# Schatten2.net
KiCad netlist of a schematic drawn in EAGLE
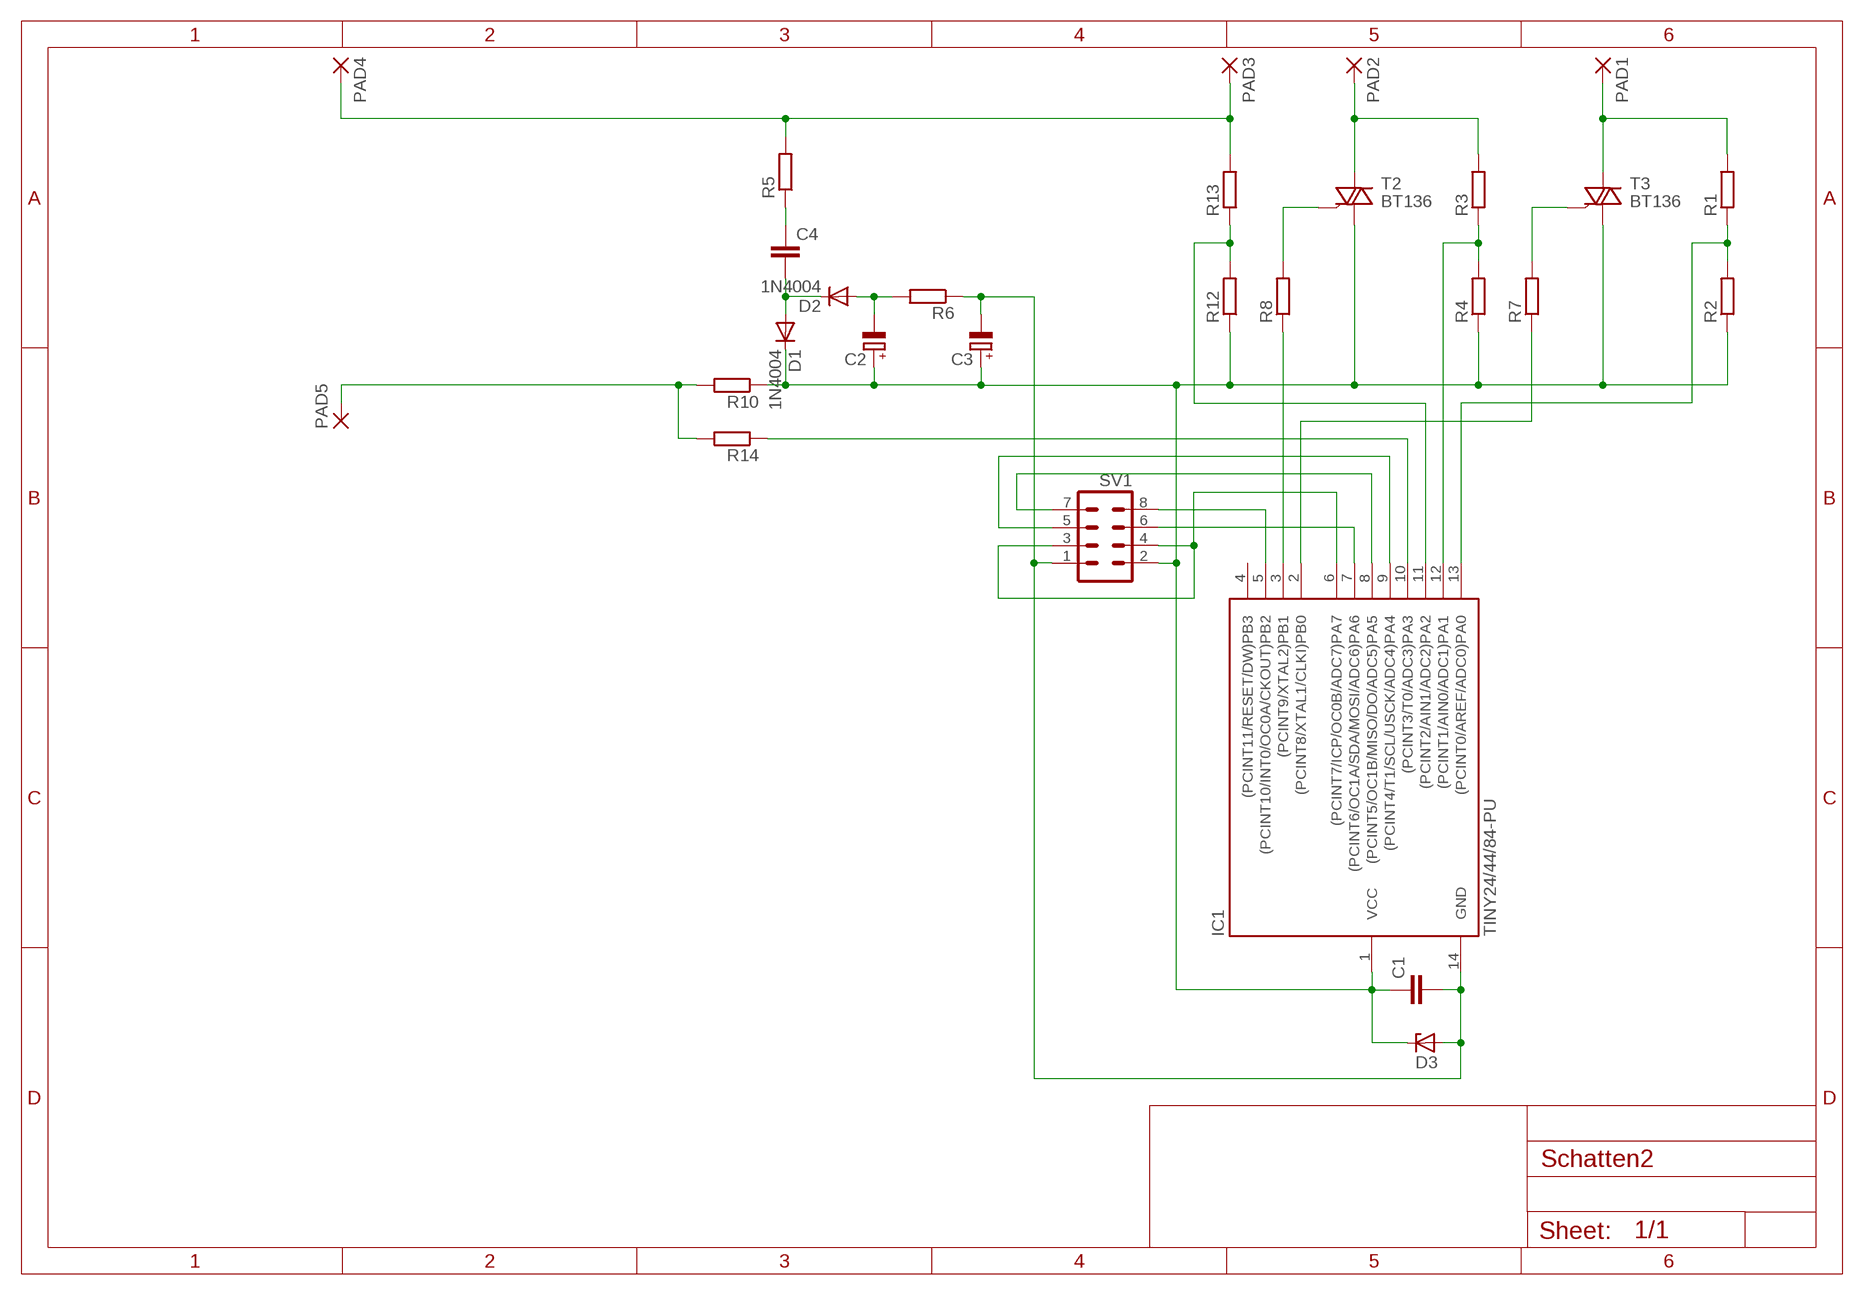
[diagram p0: schematic, sheet 1]

(export (version "E")
  (design (tool "Eeschema 10.0.6"))
  (components
    (comp (ref "C1")
      (value "C-EUC3225")
      (footprint "eagle-import:C3225")
      (libsource (lib "eagle-import") (part "C-EUC3225"))
    )
    (comp (ref "C2")
      (value "CPOL-EUE5-8.5")
      (footprint "eagle-import:E5-8,5")
      (libsource (lib "eagle-import") (part "CPOL-EUE5-8.5"))
    )
    (comp (ref "C3")
      (value "CPOL-EUE5-8.5")
      (footprint "eagle-import:E5-8,5")
      (libsource (lib "eagle-import") (part "CPOL-EUE5-8.5"))
    )
    (comp (ref "C4")
      (value "C-EU150-064X183")
      (footprint "eagle-import:C150-064X183")
      (libsource (lib "eagle-import") (part "C-EU150-064X183"))
    )
    (comp (ref "D1")
      (value "1N4004")
      (footprint "eagle-import:DO41-10")
      (libsource (lib "eagle-import") (part "1N4004"))
    )
    (comp (ref "D2")
      (value "1N4004")
      (footprint "eagle-import:DO41-10")
      (libsource (lib "eagle-import") (part "1N4004"))
    )
    (comp (ref "D3")
      (value "ZENER-DIODEZD-7.5")
      (footprint "eagle-import:ZDIO-7.5")
      (libsource (lib "eagle-import") (part "ZENER-DIODEZD-7.5"))
    )
    (comp (ref "IC1")
      (value "TINY24/44/84-PU")
      (footprint "eagle-import:DIL14")
      (libsource (lib "eagle-import") (part "TINY24/44/84-PU"))
    )
    (comp (ref "PAD1")
      (value "1,6/0,9")
      (footprint "eagle-import:1,6_0,9")
      (libsource (lib "eagle-import") (part "1,6/0,9"))
    )
    (comp (ref "PAD2")
      (value "1,6/0,9")
      (footprint "eagle-import:1,6_0,9")
      (libsource (lib "eagle-import") (part "1,6/0,9"))
    )
    (comp (ref "PAD3")
      (value "1,6/0,9")
      (footprint "eagle-import:1,6_0,9")
      (libsource (lib "eagle-import") (part "1,6/0,9"))
    )
    (comp (ref "PAD4")
      (value "1,6/0,9")
      (footprint "eagle-import:1,6_0,9")
      (libsource (lib "eagle-import") (part "1,6/0,9"))
    )
    (comp (ref "PAD5")
      (value "1,6/0,9")
      (footprint "eagle-import:1,6_0,9")
      (libsource (lib "eagle-import") (part "1,6/0,9"))
    )
    (comp (ref "R1")
      (value "R-EU_0207/10")
      (footprint "eagle-import:0207_10")
      (libsource (lib "eagle-import") (part "R-EU_0207/10"))
    )
    (comp (ref "R2")
      (value "R-EU_0207/10")
      (footprint "eagle-import:0207_10")
      (libsource (lib "eagle-import") (part "R-EU_0207/10"))
    )
    (comp (ref "R3")
      (value "R-EU_0207/10")
      (footprint "eagle-import:0207_10")
      (libsource (lib "eagle-import") (part "R-EU_0207/10"))
    )
    (comp (ref "R4")
      (value "R-EU_0207/10")
      (footprint "eagle-import:0207_10")
      (libsource (lib "eagle-import") (part "R-EU_0207/10"))
    )
    (comp (ref "R5")
      (value "R-EU_0207/10")
      (footprint "eagle-import:0207_10")
      (libsource (lib "eagle-import") (part "R-EU_0207/10"))
    )
    (comp (ref "R6")
      (value "R-EU_0207/10")
      (footprint "eagle-import:0207_10")
      (libsource (lib "eagle-import") (part "R-EU_0207/10"))
    )
    (comp (ref "R7")
      (value "R-EU_0207/10")
      (footprint "eagle-import:0207_10")
      (libsource (lib "eagle-import") (part "R-EU_0207/10"))
    )
    (comp (ref "R8")
      (value "R-EU_0207/10")
      (footprint "eagle-import:0207_10")
      (libsource (lib "eagle-import") (part "R-EU_0207/10"))
    )
    (comp (ref "R10")
      (value "R-EU_0207/10")
      (footprint "eagle-import:0207_10")
      (libsource (lib "eagle-import") (part "R-EU_0207/10"))
    )
    (comp (ref "R12")
      (value "R-EU_0207/10")
      (footprint "eagle-import:0207_10")
      (libsource (lib "eagle-import") (part "R-EU_0207/10"))
    )
    (comp (ref "R13")
      (value "R-EU_0207/10")
      (footprint "eagle-import:0207_10")
      (libsource (lib "eagle-import") (part "R-EU_0207/10"))
    )
    (comp (ref "R14")
      (value "R-EU_0207/10")
      (footprint "eagle-import:0207_10")
      (libsource (lib "eagle-import") (part "R-EU_0207/10"))
    )
    (comp (ref "SV1")
      (value "MA04-2")
      (footprint "eagle-import:MA04-2")
      (libsource (lib "eagle-import") (part "MA04-2"))
    )
    (comp (ref "T2")
      (value "BT136")
      (footprint "eagle-import:TO220AB")
      (libsource (lib "eagle-import") (part "BT136"))
    )
    (comp (ref "T3")
      (value "BT136")
      (footprint "eagle-import:TO220AB")
      (libsource (lib "eagle-import") (part "BT136"))
    )
  )
  (nets
    (net (code "1") (name "Net-(C2-Pad-)") (class "Default")
      (node (ref "C2") (pin "-") (pinfunction "-_-") (pintype "passive"))
      (node (ref "D2") (pin "A") (pinfunction "A_A") (pintype "passive"))
      (node (ref "R6") (pin "2") (pinfunction "2_2") (pintype "passive"))
    )
    (net (code "2") (name "Net-(C4-Pad1)") (class "Default")
      (node (ref "C4") (pin "1") (pinfunction "1_1") (pintype "passive"))
      (node (ref "R5") (pin "1") (pinfunction "1_1") (pintype "passive"))
    )
    (net (code "3") (name "Net-(C4-Pad2)") (class "Default")
      (node (ref "C4") (pin "2") (pinfunction "2_2") (pintype "passive"))
      (node (ref "D1") (pin "A") (pinfunction "A_A") (pintype "passive"))
      (node (ref "D2") (pin "C") (pinfunction "C_C") (pintype "passive"))
    )
    (net (code "4") (name "Net-(IC1-(PCINT0{slash}AREF{slash}ADC0)PA0)") (class "Default")
      (node (ref "IC1") (pin "13") (pinfunction "(PCINT0/AREF/ADC0)PA0_13") (pintype "bidirectional"))
      (node (ref "R1") (pin "1") (pinfunction "1_1") (pintype "passive"))
      (node (ref "R2") (pin "2") (pinfunction "2_2") (pintype "passive"))
    )
    (net (code "5") (name "Net-(IC1-(PCINT1{slash}AIN0{slash}ADC1)PA1)") (class "Default")
      (node (ref "IC1") (pin "12") (pinfunction "(PCINT1/AIN0/ADC1)PA1_12") (pintype "bidirectional"))
      (node (ref "R3") (pin "1") (pinfunction "1_1") (pintype "passive"))
      (node (ref "R4") (pin "2") (pinfunction "2_2") (pintype "passive"))
    )
    (net (code "6") (name "Net-(IC1-(PCINT2{slash}AIN1{slash}ADC2)PA2)") (class "Default")
      (node (ref "IC1") (pin "11") (pinfunction "(PCINT2/AIN1/ADC2)PA2_11") (pintype "bidirectional"))
      (node (ref "R12") (pin "2") (pinfunction "2_2") (pintype "passive"))
      (node (ref "R13") (pin "1") (pinfunction "1_1") (pintype "passive"))
    )
    (net (code "7") (name "Net-(IC1-(PCINT3{slash}T0{slash}ADC3)PA3)") (class "Default")
      (node (ref "IC1") (pin "10") (pinfunction "(PCINT3/T0/ADC3)PA3_10") (pintype "bidirectional"))
      (node (ref "R14") (pin "1") (pinfunction "1_1") (pintype "passive"))
    )
    (net (code "8") (name "Net-(IC1-(PCINT4{slash}T1{slash}SCL{slash}USCK{slash}ADC4)PA4)") (class "Default")
      (node (ref "IC1") (pin "9") (pinfunction "(PCINT4/T1/SCL/USCK/ADC4)PA4_9") (pintype "bidirectional"))
      (node (ref "SV1") (pin "5") (pinfunction "5_5") (pintype "passive"))
    )
    (net (code "9") (name "Net-(IC1-(PCINT5{slash}OC1B{slash}MISO{slash}DO{slash}ADC5)PA5)") (class "Default")
      (node (ref "IC1") (pin "8") (pinfunction "(PCINT5/OC1B/MISO/DO/ADC5)PA5_8") (pintype "bidirectional"))
      (node (ref "SV1") (pin "7") (pinfunction "7_7") (pintype "passive"))
    )
    (net (code "10") (name "Net-(IC1-(PCINT6{slash}OC1A{slash}SDA{slash}MOSI{slash}ADC6)PA6)") (class "Default")
      (node (ref "IC1") (pin "7") (pinfunction "(PCINT6/OC1A/SDA/MOSI/ADC6)PA6_7") (pintype "bidirectional"))
      (node (ref "SV1") (pin "6") (pinfunction "6_6") (pintype "passive"))
    )
    (net (code "11") (name "Net-(IC1-(PCINT7{slash}ICP{slash}OC0B{slash}ADC7)PA7)") (class "Default")
      (node (ref "IC1") (pin "6") (pinfunction "(PCINT7/ICP/OC0B/ADC7)PA7_6") (pintype "bidirectional"))
      (node (ref "SV1") (pin "3") (pinfunction "3_3") (pintype "passive"))
      (node (ref "SV1") (pin "4") (pinfunction "4_4") (pintype "passive"))
    )
    (net (code "12") (name "Net-(IC1-(PCINT8{slash}XTAL1{slash}CLKI)PB0)") (class "Default")
      (node (ref "IC1") (pin "2") (pinfunction "(PCINT8/XTAL1/CLKI)PB0_2") (pintype "bidirectional"))
      (node (ref "R7") (pin "1") (pinfunction "1_1") (pintype "passive"))
    )
    (net (code "13") (name "Net-(IC1-(PCINT9{slash}XTAL2)PB1)") (class "Default")
      (node (ref "IC1") (pin "3") (pinfunction "(PCINT9/XTAL2)PB1_3") (pintype "bidirectional"))
      (node (ref "R8") (pin "1") (pinfunction "1_1") (pintype "passive"))
    )
    (net (code "14") (name "Net-(IC1-(PCINT10{slash}INT0{slash}OC0A{slash}CKOUT)PB2)") (class "Default")
      (node (ref "IC1") (pin "5") (pinfunction "(PCINT10/INT0/OC0A/CKOUT)PB2_5") (pintype "bidirectional"))
      (node (ref "SV1") (pin "8") (pinfunction "8_8") (pintype "passive"))
    )
    (net (code "15") (name "Net-(IC1-GND)") (class "Default")
      (node (ref "C1") (pin "2") (pinfunction "2_2") (pintype "passive"))
      (node (ref "C3") (pin "-") (pinfunction "-_-") (pintype "passive"))
      (node (ref "D3") (pin "A") (pinfunction "A_A") (pintype "passive"))
      (node (ref "IC1") (pin "14") (pinfunction "GND_14") (pintype "power_in"))
      (node (ref "R6") (pin "1") (pinfunction "1_1") (pintype "passive"))
      (node (ref "SV1") (pin "1") (pinfunction "1_1") (pintype "passive"))
    )
    (net (code "16") (name "Net-(IC1-VCC)") (class "Default")
      (node (ref "C1") (pin "1") (pinfunction "1_1") (pintype "passive"))
      (node (ref "C2") (pin "+") (pinfunction "+_+") (pintype "passive"))
      (node (ref "C3") (pin "+") (pinfunction "+_+") (pintype "passive"))
      (node (ref "D1") (pin "C") (pinfunction "C_C") (pintype "passive"))
      (node (ref "D3") (pin "C") (pinfunction "C_C") (pintype "passive"))
      (node (ref "IC1") (pin "1") (pinfunction "VCC_1") (pintype "power_in"))
      (node (ref "R10") (pin "1") (pinfunction "1_1") (pintype "passive"))
      (node (ref "R12") (pin "1") (pinfunction "1_1") (pintype "passive"))
      (node (ref "R2") (pin "1") (pinfunction "1_1") (pintype "passive"))
      (node (ref "R4") (pin "1") (pinfunction "1_1") (pintype "passive"))
      (node (ref "SV1") (pin "2") (pinfunction "2_2") (pintype "passive"))
      (node (ref "T2") (pin "1") (pinfunction "A1_1") (pintype "passive"))
      (node (ref "T3") (pin "1") (pinfunction "A1_1") (pintype "passive"))
    )
    (net (code "17") (name "Net-(PAD1-P)") (class "Default")
      (node (ref "PAD1") (pin "1") (pinfunction "P_1") (pintype "passive"))
      (node (ref "R1") (pin "2") (pinfunction "2_2") (pintype "passive"))
      (node (ref "T3") (pin "2") (pinfunction "A2_2") (pintype "passive"))
    )
    (net (code "18") (name "Net-(PAD2-P)") (class "Default")
      (node (ref "PAD2") (pin "1") (pinfunction "P_1") (pintype "passive"))
      (node (ref "R3") (pin "2") (pinfunction "2_2") (pintype "passive"))
      (node (ref "T2") (pin "2") (pinfunction "A2_2") (pintype "passive"))
    )
    (net (code "19") (name "Net-(PAD3-P)") (class "Default")
      (node (ref "PAD3") (pin "1") (pinfunction "P_1") (pintype "passive"))
      (node (ref "PAD4") (pin "1") (pinfunction "P_1") (pintype "passive"))
      (node (ref "R13") (pin "2") (pinfunction "2_2") (pintype "passive"))
      (node (ref "R5") (pin "2") (pinfunction "2_2") (pintype "passive"))
    )
    (net (code "20") (name "Net-(PAD5-P)") (class "Default")
      (node (ref "PAD5") (pin "1") (pinfunction "P_1") (pintype "passive"))
      (node (ref "R10") (pin "2") (pinfunction "2_2") (pintype "passive"))
      (node (ref "R14") (pin "2") (pinfunction "2_2") (pintype "passive"))
    )
    (net (code "21") (name "Net-(T2-G)") (class "Default")
      (node (ref "R8") (pin "2") (pinfunction "2_2") (pintype "passive"))
      (node (ref "T2") (pin "3") (pinfunction "G_3") (pintype "passive"))
    )
    (net (code "22") (name "Net-(T3-G)") (class "Default")
      (node (ref "R7") (pin "2") (pinfunction "2_2") (pintype "passive"))
      (node (ref "T3") (pin "3") (pinfunction "G_3") (pintype "passive"))
    )
    (net (code "23") (name "unconnected-(IC1-(PCINT11{slash}RESET{slash}DW)PB3-Pad4)") (class "Default")
      (node (ref "IC1") (pin "4") (pinfunction "(PCINT11/RESET/DW)PB3_4") (pintype "bidirectional"))
    )
  )
)
